# FPGA1394-Test.net
KiCad netlist of a schematic drawn in Altium Designer
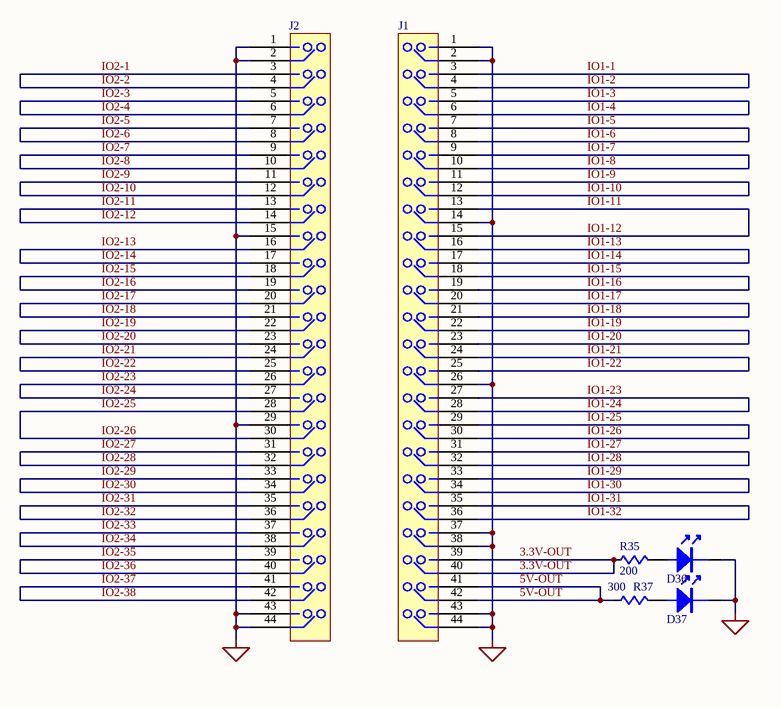
[diagram p0: FPGA1394-Test.SchDoc]

(export (version "E")
  (design (tool "Eeschema 10.0.6"))
  (components
    (comp (ref "D36") (value "LED") (footprint "LED-0805") (libsource (lib "FPGA") (part "LED")))
    (comp (ref "D37") (value "LED") (footprint "LED-0805") (libsource (lib "FPGA") (part "LED")))
    (comp (ref "J1")
      (value "HEADER 22x2-1")
      (footprint "HDR-22x2-2MM")
      (libsource (lib "QLA") (part "HEADER 22x2-1"))
    )
    (comp (ref "J2")
      (value "HEADER 22x2-1")
      (footprint "HDR-22x2-2MM")
      (libsource (lib "QLA") (part "HEADER 22x2-1"))
    )
    (comp (ref "R35") (value "200") (footprint "R0805") (libsource (lib "QLA") (part "R-MINI")))
    (comp (ref "R37") (value "300") (footprint "R0805") (libsource (lib "QLA") (part "R-MINI")))
  )
  (nets
    (net (code "1") (name "/3.3V-OUT") (class "Default")
      (node (ref "J1") (pin "39") (pinfunction "39_39") (pintype "passive"))
      (node (ref "J1") (pin "40") (pinfunction "40_40") (pintype "passive"))
      (node (ref "R35") (pin "1") (pinfunction "1_1") (pintype "passive"))
    )
    (net (code "2") (name "/5V-OUT") (class "Default")
      (node (ref "J1") (pin "41") (pinfunction "41_41") (pintype "passive"))
      (node (ref "J1") (pin "42") (pinfunction "42_42") (pintype "passive"))
      (node (ref "R37") (pin "1") (pinfunction "1_1") (pintype "passive"))
    )
    (net (code "3") (name "/IO1-1") (class "Default")
      (node (ref "J1") (pin "3") (pinfunction "3_3") (pintype "passive"))
      (node (ref "J1") (pin "4") (pinfunction "4_4") (pintype "passive"))
    )
    (net (code "4") (name "/IO1-3") (class "Default")
      (node (ref "J1") (pin "5") (pinfunction "5_5") (pintype "passive"))
      (node (ref "J1") (pin "6") (pinfunction "6_6") (pintype "passive"))
    )
    (net (code "5") (name "/IO1-5") (class "Default")
      (node (ref "J1") (pin "7") (pinfunction "7_7") (pintype "passive"))
      (node (ref "J1") (pin "8") (pinfunction "8_8") (pintype "passive"))
    )
    (net (code "6") (name "/IO1-7") (class "Default")
      (node (ref "J1") (pin "10") (pinfunction "10_10") (pintype "passive"))
      (node (ref "J1") (pin "9") (pinfunction "9_9") (pintype "passive"))
    )
    (net (code "7") (name "/IO1-10") (class "Default")
      (node (ref "J1") (pin "11") (pinfunction "11_11") (pintype "passive"))
      (node (ref "J1") (pin "12") (pinfunction "12_12") (pintype "passive"))
    )
    (net (code "8") (name "/IO1-11") (class "Default")
      (node (ref "J1") (pin "13") (pinfunction "13_13") (pintype "passive"))
      (node (ref "J1") (pin "15") (pinfunction "15_15") (pintype "passive"))
    )
    (net (code "9") (name "/IO1-13") (class "Default")
      (node (ref "J1") (pin "16") (pinfunction "16_16") (pintype "passive"))
      (node (ref "J1") (pin "17") (pinfunction "17_17") (pintype "passive"))
    )
    (net (code "10") (name "/IO1-15") (class "Default")
      (node (ref "J1") (pin "18") (pinfunction "18_18") (pintype "passive"))
      (node (ref "J1") (pin "19") (pinfunction "19_19") (pintype "passive"))
    )
    (net (code "11") (name "/IO1-17") (class "Default")
      (node (ref "J1") (pin "20") (pinfunction "20_20") (pintype "passive"))
      (node (ref "J1") (pin "21") (pinfunction "21_21") (pintype "passive"))
    )
    (net (code "12") (name "/IO1-19") (class "Default")
      (node (ref "J1") (pin "22") (pinfunction "22_22") (pintype "passive"))
      (node (ref "J1") (pin "23") (pinfunction "23_23") (pintype "passive"))
    )
    (net (code "13") (name "/IO1-21") (class "Default")
      (node (ref "J1") (pin "24") (pinfunction "24_24") (pintype "passive"))
      (node (ref "J1") (pin "25") (pinfunction "25_25") (pintype "passive"))
    )
    (net (code "14") (name "/IO1-23") (class "Default")
      (node (ref "J1") (pin "27") (pinfunction "27_27") (pintype "passive"))
      (node (ref "J1") (pin "28") (pinfunction "28_28") (pintype "passive"))
    )
    (net (code "15") (name "/IO1-25") (class "Default")
      (node (ref "J1") (pin "29") (pinfunction "29_29") (pintype "passive"))
      (node (ref "J1") (pin "30") (pinfunction "30_30") (pintype "passive"))
    )
    (net (code "16") (name "/IO1-27") (class "Default")
      (node (ref "J1") (pin "31") (pinfunction "31_31") (pintype "passive"))
      (node (ref "J1") (pin "32") (pinfunction "32_32") (pintype "passive"))
    )
    (net (code "17") (name "/IO1-29") (class "Default")
      (node (ref "J1") (pin "33") (pinfunction "33_33") (pintype "passive"))
      (node (ref "J1") (pin "34") (pinfunction "34_34") (pintype "passive"))
    )
    (net (code "18") (name "/IO1-31") (class "Default")
      (node (ref "J1") (pin "35") (pinfunction "35_35") (pintype "passive"))
      (node (ref "J1") (pin "36") (pinfunction "36_36") (pintype "passive"))
    )
    (net (code "19") (name "/IO2-1") (class "Default")
      (node (ref "J2") (pin "3") (pinfunction "3_3") (pintype "passive"))
      (node (ref "J2") (pin "4") (pinfunction "4_4") (pintype "passive"))
    )
    (net (code "20") (name "/IO2-3") (class "Default")
      (node (ref "J2") (pin "5") (pinfunction "5_5") (pintype "passive"))
      (node (ref "J2") (pin "6") (pinfunction "6_6") (pintype "passive"))
    )
    (net (code "21") (name "/IO2-5") (class "Default")
      (node (ref "J2") (pin "7") (pinfunction "7_7") (pintype "passive"))
      (node (ref "J2") (pin "8") (pinfunction "8_8") (pintype "passive"))
    )
    (net (code "22") (name "/IO2-7") (class "Default")
      (node (ref "J2") (pin "10") (pinfunction "10_10") (pintype "passive"))
      (node (ref "J2") (pin "9") (pinfunction "9_9") (pintype "passive"))
    )
    (net (code "23") (name "/IO2-10") (class "Default")
      (node (ref "J2") (pin "11") (pinfunction "11_11") (pintype "passive"))
      (node (ref "J2") (pin "12") (pinfunction "12_12") (pintype "passive"))
    )
    (net (code "24") (name "/IO2-11") (class "Default")
      (node (ref "J2") (pin "13") (pinfunction "13_13") (pintype "passive"))
      (node (ref "J2") (pin "14") (pinfunction "14_14") (pintype "passive"))
    )
    (net (code "25") (name "/IO2-13") (class "Default")
      (node (ref "J2") (pin "16") (pinfunction "16_16") (pintype "passive"))
      (node (ref "J2") (pin "17") (pinfunction "17_17") (pintype "passive"))
    )
    (net (code "26") (name "/IO2-15") (class "Default")
      (node (ref "J2") (pin "18") (pinfunction "18_18") (pintype "passive"))
      (node (ref "J2") (pin "19") (pinfunction "19_19") (pintype "passive"))
    )
    (net (code "27") (name "/IO2-17") (class "Default")
      (node (ref "J2") (pin "20") (pinfunction "20_20") (pintype "passive"))
      (node (ref "J2") (pin "21") (pinfunction "21_21") (pintype "passive"))
    )
    (net (code "28") (name "/IO2-19") (class "Default")
      (node (ref "J2") (pin "22") (pinfunction "22_22") (pintype "passive"))
      (node (ref "J2") (pin "23") (pinfunction "23_23") (pintype "passive"))
    )
    (net (code "29") (name "/IO2-21") (class "Default")
      (node (ref "J2") (pin "24") (pinfunction "24_24") (pintype "passive"))
      (node (ref "J2") (pin "25") (pinfunction "25_25") (pintype "passive"))
    )
    (net (code "30") (name "/IO2-23") (class "Default")
      (node (ref "J2") (pin "26") (pinfunction "26_26") (pintype "passive"))
      (node (ref "J2") (pin "27") (pinfunction "27_27") (pintype "passive"))
    )
    (net (code "31") (name "/IO2-25") (class "Default")
      (node (ref "J2") (pin "28") (pinfunction "28_28") (pintype "passive"))
      (node (ref "J2") (pin "30") (pinfunction "30_30") (pintype "passive"))
    )
    (net (code "32") (name "/IO2-27") (class "Default")
      (node (ref "J2") (pin "31") (pinfunction "31_31") (pintype "passive"))
      (node (ref "J2") (pin "32") (pinfunction "32_32") (pintype "passive"))
    )
    (net (code "33") (name "/IO2-29") (class "Default")
      (node (ref "J2") (pin "33") (pinfunction "33_33") (pintype "passive"))
      (node (ref "J2") (pin "34") (pinfunction "34_34") (pintype "passive"))
    )
    (net (code "34") (name "/IO2-31") (class "Default")
      (node (ref "J2") (pin "35") (pinfunction "35_35") (pintype "passive"))
      (node (ref "J2") (pin "36") (pinfunction "36_36") (pintype "passive"))
    )
    (net (code "35") (name "/IO2-33") (class "Default")
      (node (ref "J2") (pin "37") (pinfunction "37_37") (pintype "passive"))
      (node (ref "J2") (pin "38") (pinfunction "38_38") (pintype "passive"))
    )
    (net (code "36") (name "/IO2-35") (class "Default")
      (node (ref "J2") (pin "39") (pinfunction "39_39") (pintype "passive"))
      (node (ref "J2") (pin "40") (pinfunction "40_40") (pintype "passive"))
    )
    (net (code "37") (name "/IO2-37") (class "Default")
      (node (ref "J2") (pin "41") (pinfunction "41_41") (pintype "passive"))
      (node (ref "J2") (pin "42") (pinfunction "42_42") (pintype "passive"))
    )
    (net (code "38") (name "GND") (class "Default")
      (node (ref "D36") (pin "1") (pinfunction "C_1") (pintype "passive"))
      (node (ref "D37") (pin "1") (pinfunction "C_1") (pintype "passive"))
      (node (ref "J1") (pin "1") (pinfunction "1_1") (pintype "passive"))
      (node (ref "J1") (pin "14") (pinfunction "14_14") (pintype "passive"))
      (node (ref "J1") (pin "2") (pinfunction "2_2") (pintype "passive"))
      (node (ref "J1") (pin "26") (pinfunction "26_26") (pintype "passive"))
      (node (ref "J1") (pin "37") (pinfunction "37_37") (pintype "passive"))
      (node (ref "J1") (pin "38") (pinfunction "38_38") (pintype "passive"))
      (node (ref "J1") (pin "43") (pinfunction "43_43") (pintype "passive"))
      (node (ref "J1") (pin "44") (pinfunction "44_44") (pintype "passive"))
      (node (ref "J2") (pin "1") (pinfunction "1_1") (pintype "passive"))
      (node (ref "J2") (pin "15") (pinfunction "15_15") (pintype "passive"))
      (node (ref "J2") (pin "2") (pinfunction "2_2") (pintype "passive"))
      (node (ref "J2") (pin "29") (pinfunction "29_29") (pintype "passive"))
      (node (ref "J2") (pin "43") (pinfunction "43_43") (pintype "passive"))
      (node (ref "J2") (pin "44") (pinfunction "44_44") (pintype "passive"))
    )
    (net (code "39") (name "Net-(D36-A)") (class "Default")
      (node (ref "D36") (pin "2") (pinfunction "A_2") (pintype "passive"))
      (node (ref "R35") (pin "2") (pinfunction "2_2") (pintype "passive"))
    )
    (net (code "40") (name "Net-(D37-A)") (class "Default")
      (node (ref "D37") (pin "2") (pinfunction "A_2") (pintype "passive"))
      (node (ref "R37") (pin "2") (pinfunction "2_2") (pintype "passive"))
    )
  )
)
